# USB_Hub.net
KiCad netlist of a schematic drawn in Altium Designer
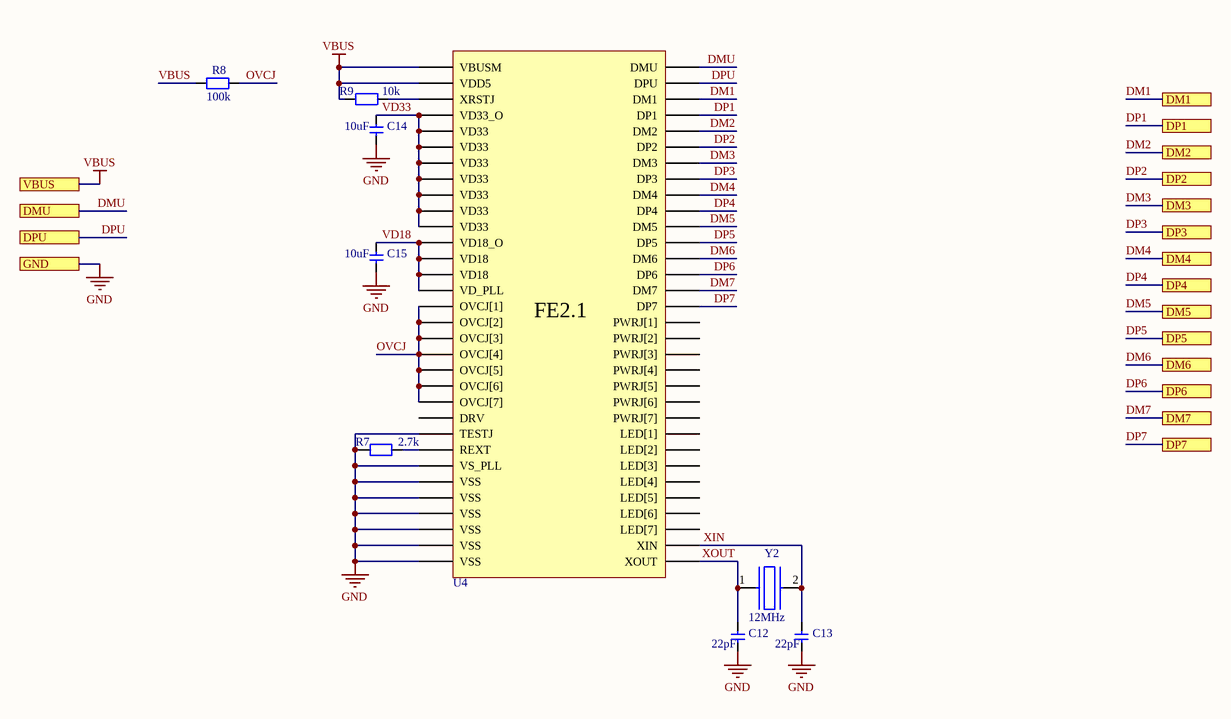
[diagram p0: USB Hub.SchDoc]

(export (version "E")
  (design (tool "Eeschema 10.0.6"))
  (components
    (comp (ref "C12")
      (value "22pF")
      (footprint "cap0603")
      (libsource (lib "AlexChistiakov") (part "Cap SMD"))
    )
    (comp (ref "C13")
      (value "22pF")
      (footprint "cap0603")
      (libsource (lib "AlexChistiakov") (part "Cap SMD"))
    )
    (comp (ref "C14")
      (value "10uF")
      (footprint "cap0603")
      (libsource (lib "AlexChistiakov") (part "Cap SMD"))
    )
    (comp (ref "C15")
      (value "10uF")
      (footprint "cap0603")
      (libsource (lib "AlexChistiakov") (part "Cap SMD"))
    )
    (comp (ref "R7")
      (value "2.7k")
      (footprint "res0603")
      (libsource (lib "AlexChistiakov") (part "Resistor SMD"))
    )
    (comp (ref "R8")
      (value "100k")
      (footprint "res0603")
      (libsource (lib "AlexChistiakov") (part "Resistor SMD"))
    )
    (comp (ref "R9")
      (value "10k")
      (footprint "res0603")
      (libsource (lib "AlexChistiakov") (part "Resistor SMD"))
    )
    (comp (ref "U4")
      (value "FE2.1")
      (footprint "LQFP64_N_1")
      (libsource (lib "AlexChistiakov") (part "FE2.1"))
    )
    (comp (ref "Y2") (value "12MHz") (libsource (lib "AlexChistiakov") (part "Quartz")))
  )
  (nets
    (net (code "1") (name "/DM1") (class "Default")
      (node (ref "U4") (pin "26") (pinfunction "DM1_26") (pintype "passive"))
    )
    (net (code "2") (name "/DM2") (class "Default")
      (node (ref "U4") (pin "23") (pinfunction "DM2_23") (pintype "passive"))
    )
    (net (code "3") (name "/DM3") (class "Default")
      (node (ref "U4") (pin "20") (pinfunction "DM3_20") (pintype "passive"))
    )
    (net (code "4") (name "/DM4") (class "Default")
      (node (ref "U4") (pin "17") (pinfunction "DM4_17") (pintype "passive"))
    )
    (net (code "5") (name "/DM5") (class "Default")
      (node (ref "U4") (pin "41") (pinfunction "DM5_41") (pintype "passive"))
    )
    (net (code "6") (name "/DM6") (class "Default")
      (node (ref "U4") (pin "44") (pinfunction "DM6_44") (pintype "passive"))
    )
    (net (code "7") (name "/DM7") (class "Default")
      (node (ref "U4") (pin "47") (pinfunction "DM7_47") (pintype "passive"))
    )
    (net (code "8") (name "/DMU") (class "Default")
      (node (ref "U4") (pin "38") (pinfunction "DMU_38") (pintype "passive"))
    )
    (net (code "9") (name "/DP1") (class "Default")
      (node (ref "U4") (pin "27") (pinfunction "DP1_27") (pintype "passive"))
    )
    (net (code "10") (name "/DP2") (class "Default")
      (node (ref "U4") (pin "24") (pinfunction "DP2_24") (pintype "passive"))
    )
    (net (code "11") (name "/DP3") (class "Default")
      (node (ref "U4") (pin "21") (pinfunction "DP3_21") (pintype "passive"))
    )
    (net (code "12") (name "/DP4") (class "Default")
      (node (ref "U4") (pin "18") (pinfunction "DP4_18") (pintype "passive"))
    )
    (net (code "13") (name "/DP5") (class "Default")
      (node (ref "U4") (pin "42") (pinfunction "DP5_42") (pintype "passive"))
    )
    (net (code "14") (name "/DP6") (class "Default")
      (node (ref "U4") (pin "45") (pinfunction "DP6_45") (pintype "passive"))
    )
    (net (code "15") (name "/DP7") (class "Default")
      (node (ref "U4") (pin "48") (pinfunction "DP7_48") (pintype "passive"))
    )
    (net (code "16") (name "/DPU") (class "Default")
      (node (ref "U4") (pin "39") (pinfunction "DPU_39") (pintype "passive"))
    )
    (net (code "17") (name "/OVCJ") (class "Default")
      (node (ref "R8") (pin "2") (pinfunction "2_2") (pintype "passive"))
      (node (ref "U4") (pin "14") (pinfunction "OVCJ[1]_14") (pintype "passive"))
      (node (ref "U4") (pin "15") (pinfunction "OVCJ[2]_15") (pintype "passive"))
      (node (ref "U4") (pin "16") (pinfunction "OVCJ[3]_16") (pintype "passive"))
      (node (ref "U4") (pin "17") (pinfunction "OVCJ[4]_17") (pintype "passive"))
      (node (ref "U4") (pin "18") (pinfunction "OVCJ[5]_18") (pintype "passive"))
      (node (ref "U4") (pin "19") (pinfunction "OVCJ[6]_19") (pintype "passive"))
      (node (ref "U4") (pin "20") (pinfunction "OVCJ[7]_20") (pintype "passive"))
    )
    (net (code "18") (name "/VD18") (class "Default")
      (node (ref "C15") (pin "2") (pinfunction "2_2") (pintype "passive"))
      (node (ref "U4") (pin "29") (pinfunction "VD_PLL_29") (pintype "passive"))
      (node (ref "U4") (pin "33") (pinfunction "VD18_O_33") (pintype "passive"))
      (node (ref "U4") (pin "36") (pinfunction "VD18_36") (pintype "passive"))
      (node (ref "U4") (pin "7") (pinfunction "VD18_7") (pintype "passive"))
    )
    (net (code "19") (name "/VD33") (class "Default")
      (node (ref "C14") (pin "2") (pinfunction "2_2") (pintype "passive"))
      (node (ref "U4") (pin "10") (pinfunction "VD33_O_10") (pintype "passive"))
      (node (ref "U4") (pin "16") (pinfunction "VD33_16") (pintype "passive"))
      (node (ref "U4") (pin "22") (pinfunction "VD33_22") (pintype "passive"))
      (node (ref "U4") (pin "28") (pinfunction "VD33_28") (pintype "passive"))
      (node (ref "U4") (pin "34") (pinfunction "VD33_34") (pintype "passive"))
      (node (ref "U4") (pin "40") (pinfunction "VD33_40") (pintype "passive"))
      (node (ref "U4") (pin "46") (pinfunction "VD33_46") (pintype "passive"))
      (node (ref "U4") (pin "56") (pinfunction "VD33_56") (pintype "passive"))
    )
    (net (code "20") (name "/XIN") (class "Default")
      (node (ref "C13") (pin "2") (pinfunction "2_2") (pintype "passive"))
      (node (ref "U4") (pin "30") (pinfunction "XIN_30") (pintype "passive"))
      (node (ref "Y2") (pin "2") (pintype "power_in"))
    )
    (net (code "21") (name "/XOUT") (class "Default")
      (node (ref "C12") (pin "2") (pinfunction "2_2") (pintype "passive"))
      (node (ref "U4") (pin "31") (pinfunction "XOUT_31") (pintype "passive"))
      (node (ref "Y2") (pin "1") (pintype "power_in"))
    )
    (net (code "22") (name "GND") (class "Default")
      (node (ref "C12") (pin "1") (pinfunction "1_1") (pintype "passive"))
      (node (ref "C13") (pin "1") (pinfunction "1_1") (pintype "passive"))
      (node (ref "C14") (pin "1") (pinfunction "1_1") (pintype "passive"))
      (node (ref "C15") (pin "1") (pinfunction "1_1") (pintype "passive"))
      (node (ref "R7") (pin "1") (pinfunction "1_1") (pintype "passive"))
      (node (ref "U4") (pin "11") (pinfunction "VSS_11") (pintype "passive"))
      (node (ref "U4") (pin "19") (pinfunction "VSS_19") (pintype "passive"))
      (node (ref "U4") (pin "25") (pinfunction "VSS_25") (pintype "passive"))
      (node (ref "U4") (pin "3") (pinfunction "TESTJ_3") (pintype "passive"))
      (node (ref "U4") (pin "32") (pinfunction "VS_PLL_32") (pintype "passive"))
      (node (ref "U4") (pin "37") (pinfunction "VSS_37") (pintype "passive"))
      (node (ref "U4") (pin "43") (pinfunction "VSS_43") (pintype "passive"))
      (node (ref "U4") (pin "49") (pinfunction "VSS_49") (pintype "passive"))
    )
    (net (code "23") (name "Net-(U4-REXT)") (class "Default")
      (node (ref "R7") (pin "2") (pinfunction "2_2") (pintype "passive"))
      (node (ref "U4") (pin "35") (pinfunction "REXT_35") (pintype "passive"))
    )
    (net (code "24") (name "Net-(U4-XRSTJ)") (class "Default")
      (node (ref "R9") (pin "2") (pinfunction "2_2") (pintype "passive"))
      (node (ref "U4") (pin "50") (pinfunction "XRSTJ_50") (pintype "passive"))
    )
    (net (code "25") (name "VBUS") (class "Default")
      (node (ref "R8") (pin "1") (pinfunction "1_1") (pintype "passive"))
      (node (ref "R9") (pin "1") (pinfunction "1_1") (pintype "passive"))
      (node (ref "U4") (pin "51") (pinfunction "VBUSM_51") (pintype "passive"))
      (node (ref "U4") (pin "9") (pinfunction "VDD5_9") (pintype "passive"))
    )
    (net (code "26") (name "unconnected-(U4-DRV-Pad2)") (class "Default")
      (node (ref "U4") (pin "2") (pinfunction "DRV_2") (pintype "passive"))
    )
    (net (code "27") (name "unconnected-(U4-LED[1]-Pad4)") (class "Default")
      (node (ref "U4") (pin "4") (pinfunction "LED[1]_4") (pintype "passive"))
    )
    (net (code "28") (name "unconnected-(U4-LED[2]-Pad5)") (class "Default")
      (node (ref "U4") (pin "5") (pinfunction "LED[2]_5") (pintype "passive"))
    )
    (net (code "29") (name "unconnected-(U4-LED[3]-Pad6)") (class "Default")
      (node (ref "U4") (pin "6") (pinfunction "LED[3]_6") (pintype "passive"))
    )
    (net (code "30") (name "unconnected-(U4-LED[4]-Pad8)") (class "Default")
      (node (ref "U4") (pin "8") (pinfunction "LED[4]_8") (pintype "passive"))
    )
    (net (code "31") (name "unconnected-(U4-LED[5]-Pad1)") (class "Default")
      (node (ref "U4") (pin "1") (pinfunction "LED[5]_1") (pintype "passive"))
    )
    (net (code "32") (name "unconnected-(U4-LED[6]-Pad64)") (class "Default")
      (node (ref "U4") (pin "64") (pinfunction "LED[6]_64") (pintype "passive"))
    )
    (net (code "33") (name "unconnected-(U4-LED[7]-Pad63)") (class "Default")
      (node (ref "U4") (pin "63") (pinfunction "LED[7]_63") (pintype "passive"))
    )
    (net (code "34") (name "unconnected-(U4-PWRJ[1]-Pad59)") (class "Default")
      (node (ref "U4") (pin "59") (pinfunction "PWRJ[1]_59") (pintype "passive"))
    )
    (net (code "35") (name "unconnected-(U4-PWRJ[2]-Pad61)") (class "Default")
      (node (ref "U4") (pin "61") (pinfunction "PWRJ[2]_61") (pintype "passive"))
    )
    (net (code "36") (name "unconnected-(U4-PWRJ[3]-Pad12)") (class "Default")
      (node (ref "U4") (pin "12") (pinfunction "PWRJ[3]_12") (pintype "passive"))
    )
    (net (code "37") (name "unconnected-(U4-PWRJ[4]-Pad14)") (class "Default")
      (node (ref "U4") (pin "14") (pinfunction "PWRJ[4]_14") (pintype "passive"))
    )
    (net (code "38") (name "unconnected-(U4-PWRJ[5]-Pad57)") (class "Default")
      (node (ref "U4") (pin "57") (pinfunction "PWRJ[5]_57") (pintype "passive"))
    )
    (net (code "39") (name "unconnected-(U4-PWRJ[6]-Pad54)") (class "Default")
      (node (ref "U4") (pin "54") (pinfunction "PWRJ[6]_54") (pintype "passive"))
    )
    (net (code "40") (name "unconnected-(U4-PWRJ[7]-Pad52)") (class "Default")
      (node (ref "U4") (pin "52") (pinfunction "PWRJ[7]_52") (pintype "passive"))
    )
  )
)
